# DC-DC_Bridge.net
KiCad netlist of a schematic drawn in Altium Designer
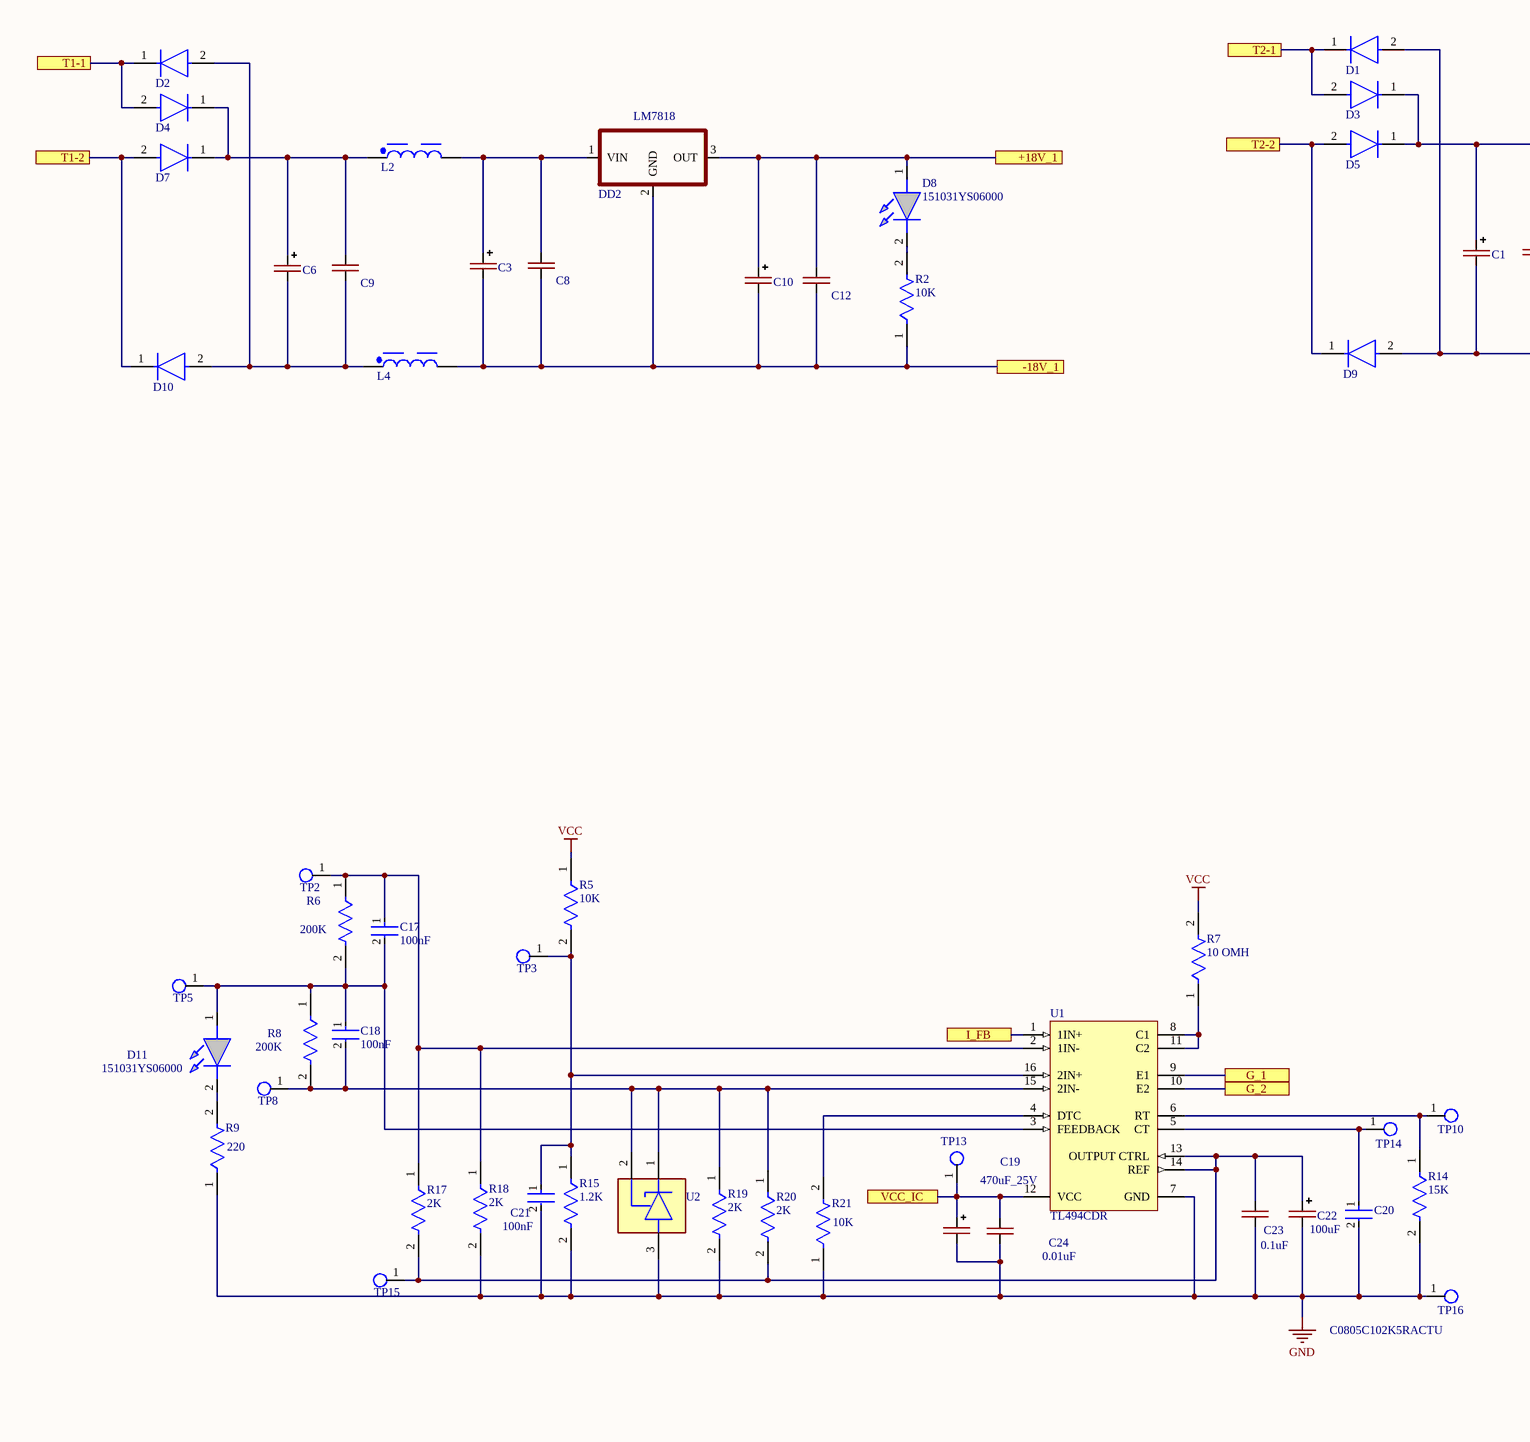
[diagram p0: DC-DC_Bridge.SchDoc, left]
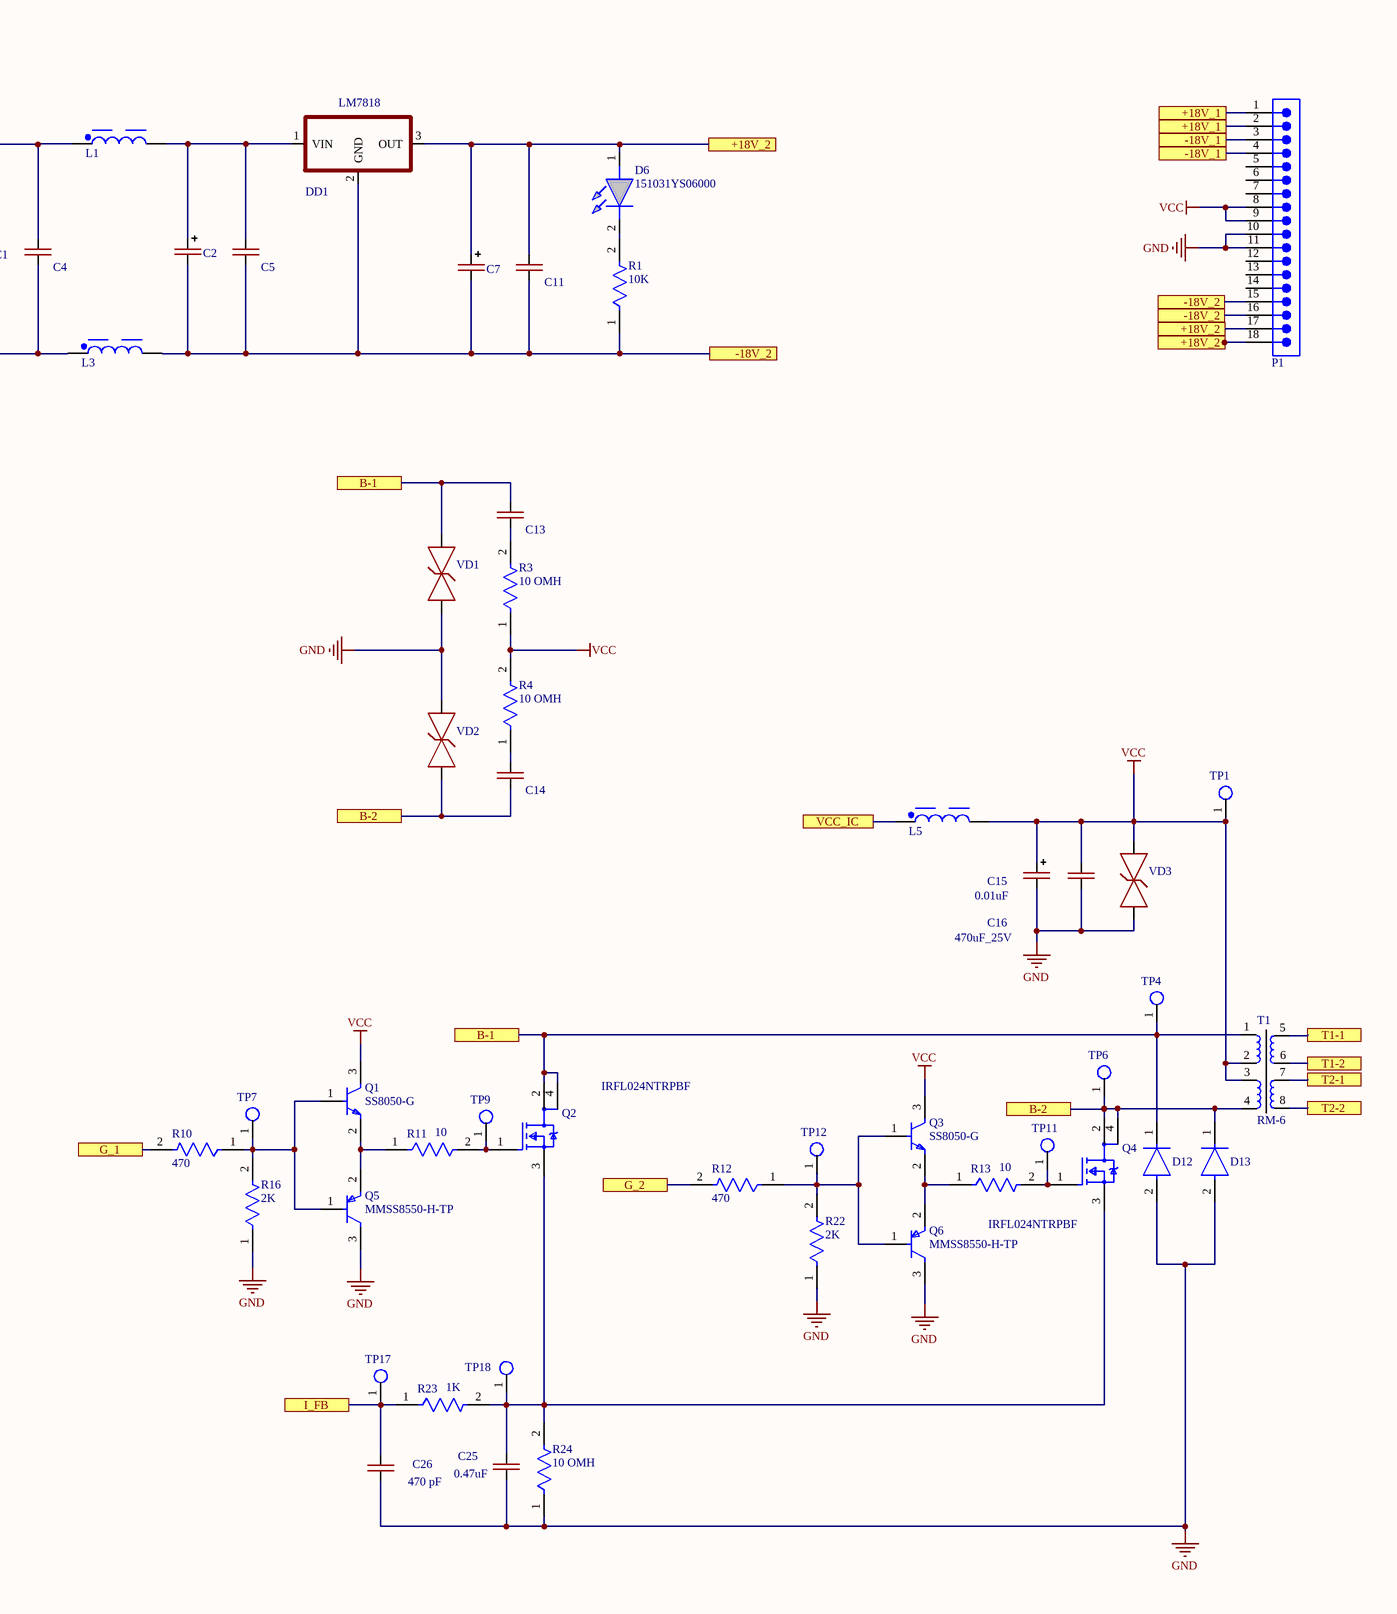
[diagram p1: DC-DC_Bridge.SchDoc, right]

(export (version "E")
  (design (tool "Eeschema 10.0.6"))
  (components
    (comp (ref "C1")
      (value "CAP-POLAR")
      (footprint "CAP_SMD_Size_G")
      (libsource (lib "PASSIVE_COMPONENTS") (part "CAP-POLAR"))
    )
    (comp (ref "C2")
      (value "CAP-POLAR")
      (footprint "CAP_SMD_Size_G")
      (libsource (lib "PASSIVE_COMPONENTS") (part "CAP-POLAR"))
    )
    (comp (ref "C3")
      (value "CAP-POLAR")
      (footprint "CAP_SMD_Size_G")
      (libsource (lib "PASSIVE_COMPONENTS") (part "CAP-POLAR"))
    )
    (comp (ref "C4")
      (value "CAP-NON-POLAR")
      (footprint "CAP-0805")
      (libsource (lib "PASSIVE_COMPONENTS") (part "CAP-NON-POLAR"))
    )
    (comp (ref "C5")
      (value "CAP-NON-POLAR")
      (footprint "CAP-0805")
      (libsource (lib "PASSIVE_COMPONENTS") (part "CAP-NON-POLAR"))
    )
    (comp (ref "C6")
      (value "CAP-POLAR")
      (footprint "CAP_SMD_Size_G")
      (libsource (lib "PASSIVE_COMPONENTS") (part "CAP-POLAR"))
    )
    (comp (ref "C7")
      (value "CAP-POLAR")
      (footprint "CAP_SMD_Size_G")
      (libsource (lib "PASSIVE_COMPONENTS") (part "CAP-POLAR"))
    )
    (comp (ref "C8")
      (value "CAP-NON-POLAR")
      (footprint "CAP-0805")
      (libsource (lib "PASSIVE_COMPONENTS") (part "CAP-NON-POLAR"))
    )
    (comp (ref "C9")
      (value "CAP-NON-POLAR")
      (footprint "CAP-0805")
      (libsource (lib "PASSIVE_COMPONENTS") (part "CAP-NON-POLAR"))
    )
    (comp (ref "C10")
      (value "CAP-POLAR")
      (footprint "CAP_SMD_Size_G")
      (libsource (lib "PASSIVE_COMPONENTS") (part "CAP-POLAR"))
    )
    (comp (ref "C11")
      (value "CAP-NON-POLAR")
      (footprint "CAP-0805")
      (libsource (lib "PASSIVE_COMPONENTS") (part "CAP-NON-POLAR"))
    )
    (comp (ref "C12")
      (value "CAP-NON-POLAR")
      (footprint "CAP-0805")
      (libsource (lib "PASSIVE_COMPONENTS") (part "CAP-NON-POLAR"))
    )
    (comp (ref "C13")
      (value "CAP-V")
      (footprint "CAP-V")
      (libsource (lib "PASSIVE_COMPONENTS") (part "CAP-V"))
    )
    (comp (ref "C14")
      (value "CAP-V")
      (footprint "CAP-V")
      (libsource (lib "PASSIVE_COMPONENTS") (part "CAP-V"))
    )
    (comp (ref "C15")
      (value "0.01uF")
      (footprint "CAP-0805")
      (libsource (lib "PASSIVE_COMPONENTS") (part "CAP-NON-POLAR"))
    )
    (comp (ref "C16")
      (value "470uF_25V")
      (footprint "CAP_SMD_Size_G")
      (libsource (lib "PASSIVE_COMPONENTS") (part "CAP-POLAR"))
    )
    (comp (ref "C17")
      (value "100nF")
      (footprint "FP-C0805C-DN-MFG")
      (description "CAP CER 10000PF 50V X7R 0805")
      (fields
        (field (name "MANUFACTURER PART NUMBER") "C0805C103J5RACTU")
        (field (name "MANUFACTURER") "KEMET")
      )
      (libsource (lib "Altium Content Vault") (part "b4654b650e69147ec39a6b967a45e02"))
    )
    (comp (ref "C18")
      (value "100nF")
      (footprint "FP-C0805C-DN-MFG")
      (description "CAP CER 10000PF 50V X7R 0805")
      (fields
        (field (name "MANUFACTURER PART NUMBER") "C0805C103J5RACTU")
        (field (name "MANUFACTURER") "KEMET")
      )
      (libsource (lib "Altium Content Vault") (part "b4654b650e69147ec39a6b967a45e02"))
    )
    (comp (ref "C19")
      (value "470uF_25V")
      (footprint "CAP_SMD_Size_G")
      (libsource (lib "PASSIVE_COMPONENTS") (part "CAP-POLAR"))
    )
    (comp (ref "C20")
      (value "C0805C102K5RACTU")
      (footprint "FP-C0805C-DN-MFG")
      (description "CAP CER 1000PF 50V X7R 0805")
      (fields
        (field (name "OCTOPART") "https://octopart.com/c0805c102k5ractu-kemet-93010")
        (field (name "TOLERANCE") "0.1")
      )
      (libsource (lib "Altium Content Vault") (part "b4654b650e69147ec39a6b967a45e02"))
    )
    (comp (ref "C21")
      (value "100nF")
      (footprint "FP-C0805C-DN-MFG")
      (description "CAP CER 10000PF 50V X7R 0805")
      (fields
        (field (name "MANUFACTURER PART NUMBER") "C0805C103J5RACTU")
        (field (name "MANUFACTURER") "KEMET")
      )
      (libsource (lib "Altium Content Vault") (part "b4654b650e69147ec39a6b967a45e02"))
    )
    (comp (ref "C22")
      (value "100uF")
      (footprint "CAP-TAN-D")
      (libsource (lib "PASSIVE_COMPONENTS") (part "CAP-POLAR"))
    )
    (comp (ref "C23")
      (value "0.1uF")
      (footprint "CAP-0805")
      (libsource (lib "PASSIVE_COMPONENTS") (part "CAP-NON-POLAR"))
    )
    (comp (ref "C24")
      (value "0.01uF")
      (footprint "CAP-0805")
      (libsource (lib "PASSIVE_COMPONENTS") (part "CAP-NON-POLAR"))
    )
    (comp (ref "C25")
      (value "0.47uF")
      (footprint "CAP-0805")
      (libsource (lib "PASSIVE_COMPONENTS") (part "CAP-NON-POLAR"))
    )
    (comp (ref "C26")
      (value "470 pF")
      (footprint "CAP-0805")
      (libsource (lib "PASSIVE_COMPONENTS") (part "CAP-NON-POLAR"))
    )
    (comp (ref "D1") (value "US1G") (footprint "DO-214AA") (libsource (lib "Diodes") (part "US1G")))
    (comp (ref "D2") (value "US1G") (footprint "DO-214AA") (libsource (lib "Diodes") (part "US1G")))
    (comp (ref "D3") (value "US1G") (footprint "DO-214AA") (libsource (lib "Diodes") (part "US1G")))
    (comp (ref "D4") (value "US1G") (footprint "DO-214AA") (libsource (lib "Diodes") (part "US1G")))
    (comp (ref "D5") (value "US1G") (footprint "DO-214AA") (libsource (lib "Diodes") (part "US1G")))
    (comp (ref "D6")
      (value "151031YS06000")
      (footprint "LED_RED")
      (description "WURTH ELEKTRONIK - 151031YS06000 - LED, Yellow, Through Hole, T-1 (3mm), 30 mA, 2 V, 590 nm")
      (fields (field (name "MOUSER PART NUMBER") "710-151031YS06000"))
      (libsource (lib "Optic-LED") (part "LED"))
    )
    (comp (ref "D7") (value "US1G") (footprint "DO-214AA") (libsource (lib "Diodes") (part "US1G")))
    (comp (ref "D8")
      (value "151031YS06000")
      (footprint "LED_RED")
      (description "WURTH ELEKTRONIK - 151031YS06000 - LED, Yellow, Through Hole, T-1 (3mm), 30 mA, 2 V, 590 nm")
      (fields (field (name "MOUSER PART NUMBER") "710-151031YS06000"))
      (libsource (lib "Optic-LED") (part "LED"))
    )
    (comp (ref "D9") (value "US1G") (footprint "DO-214AA") (libsource (lib "Diodes") (part "US1G")))
    (comp (ref "D10") (value "US1G") (footprint "DO-214AA") (libsource (lib "Diodes") (part "US1G")))
    (comp (ref "D11")
      (value "151031YS06000")
      (footprint "LED_RED")
      (description "WURTH ELEKTRONIK - 151031YS06000 - LED, Yellow, Through Hole, T-1 (3mm), 30 mA, 2 V, 590 nm")
      (fields (field (name "MOUSER PART NUMBER") "710-151031YS06000"))
      (libsource (lib "Optic-LED") (part "LED"))
    )
    (comp (ref "D12") (value "US1G") (footprint "DO-214AA") (libsource (lib "Diodes") (part "US1G")))
    (comp (ref "D13") (value "US1G") (footprint "DO-214AA") (libsource (lib "Diodes") (part "US1G")))
    (comp (ref "DD1")
      (value "LM7818")
      (footprint "TO-252")
      (libsource (lib "LM7818__TO-252") (part "LM7818"))
    )
    (comp (ref "DD2")
      (value "LM7818")
      (footprint "TO-252")
      (libsource (lib "LM7818__TO-252") (part "LM7818"))
    )
    (comp (ref "L1")
      (value "390µH, 0.38A")
      (footprint "WE-PD2_7850")
      (description "WE-PD2 SMT Power Inductor, size 7850, 390µH, 0.38A, 1.77Ω")
      (fields
        (field (name "MANUFACTURER PART NUMBER") "744775239")
        (field (name "MANUFACTURER") "Wurth Elektronik")
      )
      (libsource (lib "WE-PD2 (rev22d)") (part "744775239"))
    )
    (comp (ref "L2")
      (value "390µH, 0.38A")
      (footprint "WE-PD2_7850")
      (description "WE-PD2 SMT Power Inductor, size 7850, 390µH, 0.38A, 1.77Ω")
      (fields
        (field (name "MANUFACTURER PART NUMBER") "744775239")
        (field (name "MANUFACTURER") "Wurth Elektronik")
      )
      (libsource (lib "WE-PD2 (rev22d)") (part "744775239"))
    )
    (comp (ref "L3")
      (value "390µH, 0.38A")
      (footprint "WE-PD2_7850")
      (description "WE-PD2 SMT Power Inductor, size 7850, 390µH, 0.38A, 1.77Ω")
      (fields
        (field (name "MANUFACTURER PART NUMBER") "744775239")
        (field (name "MANUFACTURER") "Wurth Elektronik")
      )
      (libsource (lib "WE-PD2 (rev22d)") (part "744775239"))
    )
    (comp (ref "L4")
      (value "390µH, 0.38A")
      (footprint "WE-PD2_7850")
      (description "WE-PD2 SMT Power Inductor, size 7850, 390µH, 0.38A, 1.77Ω")
      (fields
        (field (name "MANUFACTURER PART NUMBER") "744775239")
        (field (name "MANUFACTURER") "Wurth Elektronik")
      )
      (libsource (lib "WE-PD2 (rev22d)") (part "744775239"))
    )
    (comp (ref "L5")
      (value "390µH, 0.38A")
      (footprint "WE-PD2_7850")
      (description "WE-PD2 SMT Power Inductor, size 7850, 390µH, 0.38A, 1.77Ω")
      (fields
        (field (name "MANUFACTURER PART NUMBER") "744775239")
        (field (name "MANUFACTURER") "Wurth Elektronik")
      )
      (libsource (lib "WE-PD2 (rev22d)") (part "744775239"))
    )
    (comp (ref "P1")
      (value "61301811021")
      (footprint "61301811021")
      (description "WR-PHD Pin Header, THT, Angled, pitch 2.54mm, 1 Row, 18P")
      (fields (field (name "MANUFACTURER") "Wurth Elektronik"))
      (libsource (lib "Altium_WR-PHD (rev22b)") (part "61301811021"))
    )
    (comp (ref "Q1")
      (value "SS8050-G")
      (footprint "FP-SS8050-G-MFG")
      (description "NPN TRANSISTOR 1.5A 40V SOT-23 R")
      (libsource (lib "Altium Content Vault") (part "2a1388f82443b098dcd57d24ac7632d"))
    )
    (comp (ref "Q2")
      (value "IRFL024NTRPBF")
      (footprint "FP-PG-SOT223-3-IPC_B")
      (description "MOSFET N-CH 55V 2.8A SOT223")
      (libsource (lib "Altium Content Vault") (part "7f70c8421781a2c4d0598199639518f"))
    )
    (comp (ref "Q3")
      (value "SS8050-G")
      (footprint "FP-SS8050-G-MFG")
      (description "NPN TRANSISTOR 1.5A 40V SOT-23 R")
      (libsource (lib "Altium Content Vault") (part "2a1388f82443b098dcd57d24ac7632d"))
    )
    (comp (ref "Q4")
      (value "IRFL024NTRPBF")
      (footprint "FP-PG-SOT223-3-IPC_B")
      (description "MOSFET N-CH 55V 2.8A SOT223")
      (libsource (lib "Altium Content Vault") (part "7f70c8421781a2c4d0598199639518f"))
    )
    (comp (ref "Q5")
      (value "MMSS8550-H-TP")
      (footprint "FP-SOT-23-IPC_B")
      (description "TRANS PNP 25V 1.5A SOT23")
      (libsource (lib "Altium Content Vault") (part "0e8486ed3b47d9c69b8404ba87cf0f7"))
    )
    (comp (ref "Q6")
      (value "MMSS8550-H-TP")
      (footprint "FP-SOT-23-IPC_B")
      (description "TRANS PNP 25V 1.5A SOT23")
      (libsource (lib "Altium Content Vault") (part "0e8486ed3b47d9c69b8404ba87cf0f7"))
    )
    (comp (ref "R1")
      (value "10K")
      (footprint "RES-0805")
      (libsource (lib "PASSIVE_COMPONENTS") (part "RES-CONST"))
    )
    (comp (ref "R2")
      (value "10K")
      (footprint "RES-0805")
      (libsource (lib "PASSIVE_COMPONENTS") (part "RES-CONST"))
    )
    (comp (ref "R3")
      (value "10 OMH")
      (footprint "RES-1206")
      (libsource (lib "PASSIVE_COMPONENTS") (part "RES-CONST"))
    )
    (comp (ref "R4")
      (value "10 OMH")
      (footprint "RES-1206")
      (libsource (lib "PASSIVE_COMPONENTS") (part "RES-CONST"))
    )
    (comp (ref "R5")
      (value "10K")
      (footprint "FP-CRCW0805-e3-MFG")
      (description "RES Thick Film, 2kΩ, 1%, 0.125W, 100ppm/°C, 0805")
      (fields (field (name "TOLERANCE") "1%"))
      (libsource (lib "Pasive_components") (part "CMP-2001-04908-2"))
    )
    (comp (ref "R6")
      (value "200K")
      (footprint "FP-CRCW0805-e3-MFG")
      (description "RES Thick Film, 2kΩ, 1%, 0.125W, 100ppm/°C, 0805")
      (fields (field (name "TOLERANCE") "1%"))
      (libsource (lib "Pasive_components") (part "CMP-2001-04908-2"))
    )
    (comp (ref "R7")
      (value "10 OMH")
      (footprint "RES-1206")
      (libsource (lib "PASSIVE_COMPONENTS") (part "RES-CONST"))
    )
    (comp (ref "R8")
      (value "200K")
      (footprint "FP-CRCW0805-e3-MFG")
      (description "RES Thick Film, 2kΩ, 1%, 0.125W, 100ppm/°C, 0805")
      (fields (field (name "TOLERANCE") "1%"))
      (libsource (lib "Pasive_components") (part "CMP-2001-04908-2"))
    )
    (comp (ref "R9")
      (value "220")
      (footprint "RES-0805")
      (libsource (lib "PASSIVE_COMPONENTS") (part "RES-CONST"))
    )
    (comp (ref "R10")
      (value "470")
      (footprint "RES-0805")
      (libsource (lib "PASSIVE_COMPONENTS") (part "RES-CONST"))
    )
    (comp (ref "R11")
      (value "10")
      (footprint "RES-0805")
      (libsource (lib "PASSIVE_COMPONENTS") (part "RES-CONST"))
    )
    (comp (ref "R12")
      (value "470")
      (footprint "RES-0805")
      (libsource (lib "PASSIVE_COMPONENTS") (part "RES-CONST"))
    )
    (comp (ref "R13")
      (value "10")
      (footprint "RES-0805")
      (libsource (lib "PASSIVE_COMPONENTS") (part "RES-CONST"))
    )
    (comp (ref "R14")
      (value "15K")
      (footprint "FP-CRCW0805-e3-MFG")
      (description "RES Thick Film, 15kΩ, 1%, 0.125W, 100ppm/°C, 0805")
      (fields (field (name "TOLERANCE") "1%"))
      (libsource (lib "Pasive_components") (part "CMP-2001-04908-2"))
    )
    (comp (ref "R15")
      (value "1.2K")
      (footprint "FP-CRCW0805-e3-MFG")
      (description "RES Thick Film, 2kΩ, 1%, 0.125W, 100ppm/°C, 0805")
      (fields (field (name "TOLERANCE") "1%"))
      (libsource (lib "Pasive_components") (part "CMP-2001-04908-2"))
    )
    (comp (ref "R16")
      (value "2K")
      (footprint "RES-0805")
      (libsource (lib "PASSIVE_COMPONENTS") (part "RES-CONST"))
    )
    (comp (ref "R17")
      (value "2K")
      (footprint "FP-CRCW0805-e3-MFG")
      (description "RES Thick Film, 2kΩ, 1%, 0.125W, 100ppm/°C, 0805")
      (fields (field (name "TOLERANCE") "1%"))
      (libsource (lib "Pasive_components") (part "CMP-2001-04908-2"))
    )
    (comp (ref "R18")
      (value "2K")
      (footprint "FP-CRCW0805-e3-MFG")
      (description "RES Thick Film, 82kΩ, 1%, 0.125W, 100ppm/°C, 0805")
      (fields (field (name "TOLERANCE") "1%"))
      (libsource (lib "Pasive_components") (part "CMP-2001-04908-2"))
    )
    (comp (ref "R19")
      (value "2K")
      (footprint "FP-CRCW0805-e3-MFG")
      (description "RES Thick Film, 2kΩ, 1%, 0.125W, 100ppm/°C, 0805")
      (fields (field (name "TOLERANCE") "1%"))
      (libsource (lib "Pasive_components") (part "CMP-2001-04908-2"))
    )
    (comp (ref "R20")
      (value "2K")
      (footprint "FP-CRCW0805-e3-MFG")
      (description "RES Thick Film, 2kΩ, 1%, 0.125W, 100ppm/°C, 0805")
      (fields (field (name "TOLERANCE") "1%"))
      (libsource (lib "Pasive_components") (part "CMP-2001-04908-2"))
    )
    (comp (ref "R21")
      (value "10K")
      (footprint "RES-0805")
      (libsource (lib "PASSIVE_COMPONENTS") (part "RES-CONST"))
    )
    (comp (ref "R22")
      (value "2K")
      (footprint "RES-0805")
      (libsource (lib "PASSIVE_COMPONENTS") (part "RES-CONST"))
    )
    (comp (ref "R23")
      (value "1K")
      (footprint "RES-0805")
      (libsource (lib "PASSIVE_COMPONENTS") (part "RES-CONST"))
    )
    (comp (ref "R24")
      (value "10 OMH")
      (footprint "RES-2512")
      (libsource (lib "PASSIVE_COMPONENTS") (part "RES-CONST"))
    )
    (comp (ref "T1")
      (value "RM-6")
      (footprint "TRANS_RM6")
      (libsource (lib "Transformers") (part "RM_6_12-12-18-18"))
    )
    (comp (ref "TP1")
      (value "~")
      (footprint "Test_Point")
      (description "Test_Point")
      (libsource (lib "Connectors") (part "TP_PCB?"))
    )
    (comp (ref "TP2")
      (value "Test_Point_PCB")
      (footprint "Test_Point")
      (description "Test_Point")
      (libsource (lib "Test_Point") (part "TP_PCB?"))
    )
    (comp (ref "TP3")
      (value "Test_Point_PCB")
      (footprint "Test_Point")
      (description "Test_Point")
      (libsource (lib "Test_Point") (part "TP_PCB?"))
    )
    (comp (ref "TP4")
      (value "~")
      (footprint "Test_Point")
      (description "Test_Point")
      (libsource (lib "Connectors") (part "TP_PCB?"))
    )
    (comp (ref "TP5")
      (value "Test_Point_PCB")
      (footprint "Test_Point")
      (description "Test_Point")
      (libsource (lib "Test_Point") (part "TP_PCB?"))
    )
    (comp (ref "TP6")
      (value "~")
      (footprint "Test_Point")
      (description "Test_Point")
      (libsource (lib "Connectors") (part "TP_PCB?"))
    )
    (comp (ref "TP7")
      (value "~")
      (footprint "Test_Point")
      (description "Test_Point")
      (libsource (lib "Connectors") (part "TP_PCB?"))
    )
    (comp (ref "TP8")
      (value "~")
      (footprint "Test_Point")
      (description "Test_Point")
      (libsource (lib "Connectors") (part "TP_PCB?"))
    )
    (comp (ref "TP9")
      (value "~")
      (footprint "Test_Point")
      (description "Test_Point")
      (libsource (lib "Connectors") (part "TP_PCB?"))
    )
    (comp (ref "TP10")
      (value "~")
      (footprint "Test_Point")
      (description "Test_Point")
      (libsource (lib "Connectors") (part "TP_PCB?"))
    )
    (comp (ref "TP11")
      (value "~")
      (footprint "Test_Point")
      (description "Test_Point")
      (libsource (lib "Connectors") (part "TP_PCB?"))
    )
    (comp (ref "TP12")
      (value "~")
      (footprint "Test_Point")
      (description "Test_Point")
      (libsource (lib "Connectors") (part "TP_PCB?"))
    )
    (comp (ref "TP13")
      (value "~")
      (footprint "Test_Point")
      (description "Test_Point")
      (libsource (lib "Connectors") (part "TP_PCB?"))
    )
    (comp (ref "TP14")
      (value "Test_Point_PCB")
      (footprint "Test_Point")
      (description "Test_Point")
      (libsource (lib "Test_Point") (part "TP_PCB?"))
    )
    (comp (ref "TP15")
      (value "Test_Point_PCB")
      (footprint "Test_Point")
      (description "Test_Point")
      (libsource (lib "Test_Point") (part "TP_PCB?"))
    )
    (comp (ref "TP16")
      (value "~")
      (footprint "Test_Point")
      (description "Test_Point")
      (libsource (lib "Connectors") (part "TP_PCB?"))
    )
    (comp (ref "TP17")
      (value "~")
      (footprint "Test_Point")
      (description "Test_Point")
      (libsource (lib "Connectors") (part "TP_PCB?"))
    )
    (comp (ref "TP18")
      (value "~")
      (footprint "Test_Point")
      (description "Test_Point")
      (libsource (lib "Connectors") (part "TP_PCB?"))
    )
    (comp (ref "U1")
      (value "TL494CDR")
      (footprint "D0016A_N")
      (fields (field (name "MANUFACTURER") "Texas Instruments"))
      (libsource (lib "Altium Content Vault") (part "TI-494D16"))
    )
    (comp (ref "U2")
      (value "TL431")
      (footprint "TL431_SOT-23-3(A)")
      (description "TL431_SOT-23-3")
      (libsource (lib "Diodes") (part "TL431_SOT-23-3"))
    )
    (comp (ref "VD1")
      (value "Suppressor")
      (footprint "P6KE350CA")
      (libsource (lib "Diodes") (part "Suppressor"))
    )
    (comp (ref "VD2")
      (value "Suppressor")
      (footprint "P6KE350CA")
      (libsource (lib "Diodes") (part "Suppressor"))
    )
    (comp (ref "VD3")
      (value "Suppressor")
      (footprint "DO-214AA")
      (libsource (lib "Diodes") (part "Suppressor"))
    )
  )
  (nets
    (net (code "1") (name "/+18V_1") (class "Default")
      (node (ref "C10") (pin "1") (pinfunction "+_1") (pintype "passive"))
      (node (ref "C12") (pin "2") (pinfunction "2_2") (pintype "passive"))
      (node (ref "D8") (pin "1") (pinfunction "A_1") (pintype "passive"))
      (node (ref "DD2") (pin "3") (pinfunction "OUT_3") (pintype "passive"))
      (node (ref "P1") (pin "1") (pinfunction "1_1") (pintype "passive"))
      (node (ref "P1") (pin "2") (pinfunction "2_2") (pintype "passive"))
    )
    (net (code "2") (name "/+18V_2") (class "Default")
      (node (ref "C11") (pin "2") (pinfunction "2_2") (pintype "passive"))
      (node (ref "C7") (pin "1") (pinfunction "+_1") (pintype "passive"))
      (node (ref "D6") (pin "1") (pinfunction "A_1") (pintype "passive"))
      (node (ref "DD1") (pin "3") (pinfunction "OUT_3") (pintype "passive"))
      (node (ref "P1") (pin "17") (pinfunction "17_17") (pintype "passive"))
      (node (ref "P1") (pin "18") (pinfunction "18_18") (pintype "passive"))
    )
    (net (code "3") (name "/-18V_1") (class "Default")
      (node (ref "C10") (pin "2") (pinfunction "-_2") (pintype "passive"))
      (node (ref "C12") (pin "1") (pinfunction "1_1") (pintype "passive"))
      (node (ref "C3") (pin "2") (pinfunction "-_2") (pintype "passive"))
      (node (ref "C8") (pin "1") (pinfunction "1_1") (pintype "passive"))
      (node (ref "DD2") (pin "2") (pinfunction "GND_2") (pintype "passive"))
      (node (ref "L4") (pin "2") (pinfunction "2_2") (pintype "passive"))
      (node (ref "P1") (pin "3") (pinfunction "3_3") (pintype "passive"))
      (node (ref "P1") (pin "4") (pinfunction "4_4") (pintype "passive"))
      (node (ref "R2") (pin "1") (pinfunction "1_1") (pintype "passive"))
    )
    (net (code "4") (name "/-18V_2") (class "Default")
      (node (ref "C11") (pin "1") (pinfunction "1_1") (pintype "passive"))
      (node (ref "C2") (pin "2") (pinfunction "-_2") (pintype "passive"))
      (node (ref "C5") (pin "1") (pinfunction "1_1") (pintype "passive"))
      (node (ref "C7") (pin "2") (pinfunction "-_2") (pintype "passive"))
      (node (ref "DD1") (pin "2") (pinfunction "GND_2") (pintype "passive"))
      (node (ref "L3") (pin "2") (pinfunction "2_2") (pintype "passive"))
      (node (ref "P1") (pin "15") (pinfunction "15_15") (pintype "passive"))
      (node (ref "P1") (pin "16") (pinfunction "16_16") (pintype "passive"))
      (node (ref "R1") (pin "1") (pinfunction "1_1") (pintype "passive"))
    )
    (net (code "5") (name "/B-1") (class "Default")
      (node (ref "C13") (pin "2") (pinfunction "2_2") (pintype "passive"))
      (node (ref "D12") (pin "1") (pinfunction "C_1") (pintype "passive"))
      (node (ref "Q2") (pin "2") (pinfunction "D_2") (pintype "passive"))
      (node (ref "Q2") (pin "4") (pinfunction "D_4") (pintype "passive"))
      (node (ref "T1") (pin "1") (pinfunction "1_1") (pintype "passive"))
      (node (ref "TP4") (pin "1") (pinfunction "G9_1") (pintype "passive"))
      (node (ref "VD1") (pin "2") (pinfunction "A_2") (pintype "passive"))
    )
    (net (code "6") (name "/B-2") (class "Default")
      (node (ref "C14") (pin "1") (pinfunction "1_1") (pintype "passive"))
      (node (ref "D13") (pin "1") (pinfunction "C_1") (pintype "passive"))
      (node (ref "Q4") (pin "2") (pinfunction "D_2") (pintype "passive"))
      (node (ref "Q4") (pin "4") (pinfunction "D_4") (pintype "passive"))
      (node (ref "T1") (pin "4") (pinfunction "4_4") (pintype "passive"))
      (node (ref "TP6") (pin "1") (pinfunction "G9_1") (pintype "passive"))
      (node (ref "VD2") (pin "1") (pinfunction "C_1") (pintype "passive"))
    )
    (net (code "7") (name "/G_1") (class "Default")
      (node (ref "R10") (pin "2") (pinfunction "2_2") (pintype "passive"))
      (node (ref "U1") (pin "9") (pinfunction "E1_9") (pintype "passive"))
    )
    (net (code "8") (name "/G_2") (class "Default")
      (node (ref "R12") (pin "2") (pinfunction "2_2") (pintype "passive"))
      (node (ref "U1") (pin "10") (pinfunction "E2_10") (pintype "passive"))
    )
    (net (code "9") (name "/I_FB") (class "Default")
      (node (ref "C26") (pin "2") (pinfunction "2_2") (pintype "passive"))
      (node (ref "R23") (pin "1") (pinfunction "1_1") (pintype "passive"))
      (node (ref "TP17") (pin "1") (pinfunction "G9_1") (pintype "passive"))
      (node (ref "U1") (pin "1") (pinfunction "1IN+_1") (pintype "input"))
    )
    (net (code "10") (name "/T1-1") (class "Default")
      (node (ref "D2") (pin "1") (pinfunction "C_1") (pintype "passive"))
      (node (ref "D4") (pin "2") (pinfunction "A_2") (pintype "passive"))
      (node (ref "T1") (pin "5") (pinfunction "5_5") (pintype "passive"))
    )
    (net (code "11") (name "/T1-2") (class "Default")
      (node (ref "D10") (pin "1") (pinfunction "C_1") (pintype "passive"))
      (node (ref "D7") (pin "2") (pinfunction "A_2") (pintype "passive"))
      (node (ref "T1") (pin "6") (pinfunction "6_6") (pintype "passive"))
    )
    (net (code "12") (name "/T2-1") (class "Default")
      (node (ref "D1") (pin "1") (pinfunction "C_1") (pintype "passive"))
      (node (ref "D3") (pin "2") (pinfunction "A_2") (pintype "passive"))
      (node (ref "T1") (pin "7") (pinfunction "7_7") (pintype "passive"))
    )
    (net (code "13") (name "/T2-2") (class "Default")
      (node (ref "D5") (pin "2") (pinfunction "A_2") (pintype "passive"))
      (node (ref "D9") (pin "1") (pinfunction "C_1") (pintype "passive"))
      (node (ref "T1") (pin "8") (pinfunction "8_8") (pintype "passive"))
    )
    (net (code "14") (name "/VCC_IC") (class "Default")
      (node (ref "C19") (pin "1") (pinfunction "+_1") (pintype "passive"))
      (node (ref "C24") (pin "2") (pinfunction "2_2") (pintype "passive"))
      (node (ref "L5") (pin "1") (pinfunction "1_1") (pintype "passive"))
      (node (ref "TP13") (pin "1") (pinfunction "G9_1") (pintype "passive"))
      (node (ref "U1") (pin "12") (pinfunction "VCC_12") (pintype "power_in"))
    )
    (net (code "15") (name "GND") (class "Default")
      (node (ref "C15") (pin "1") (pinfunction "1_1") (pintype "passive"))
      (node (ref "C16") (pin "2") (pinfunction "-_2") (pintype "passive"))
      (node (ref "C19") (pin "2") (pinfunction "-_2") (pintype "passive"))
      (node (ref "C20") (pin "2") (pinfunction "2_2") (pintype "passive"))
      (node (ref "C21") (pin "2") (pinfunction "2_2") (pintype "passive"))
      (node (ref "C22") (pin "2") (pinfunction "-_2") (pintype "passive"))
      (node (ref "C23") (pin "1") (pinfunction "1_1") (pintype "passive"))
      (node (ref "C24") (pin "1") (pinfunction "1_1") (pintype "passive"))
      (node (ref "C25") (pin "1") (pinfunction "1_1") (pintype "passive"))
      (node (ref "C26") (pin "1") (pinfunction "1_1") (pintype "passive"))
      (node (ref "D12") (pin "2") (pinfunction "A_2") (pintype "passive"))
      (node (ref "D13") (pin "2") (pinfunction "A_2") (pintype "passive"))
      (node (ref "P1") (pin "10") (pinfunction "10_10") (pintype "passive"))
      (node (ref "P1") (pin "11") (pinfunction "11_11") (pintype "passive"))
      (node (ref "Q5") (pin "3") (pinfunction "C_3") (pintype "passive"))
      (node (ref "Q6") (pin "3") (pinfunction "C_3") (pintype "passive"))
      (node (ref "R14") (pin "2") (pinfunction "2_2") (pintype "passive"))
      (node (ref "R15") (pin "2") (pinfunction "2_2") (pintype "passive"))
      (node (ref "R16") (pin "1") (pinfunction "1_1") (pintype "passive"))
      (node (ref "R18") (pin "2") (pinfunction "2_2") (pintype "passive"))
      (node (ref "R19") (pin "2") (pinfunction "2_2") (pintype "passive"))
      (node (ref "R21") (pin "1") (pinfunction "1_1") (pintype "passive"))
      (node (ref "R22") (pin "1") (pinfunction "1_1") (pintype "passive"))
      (node (ref "R24") (pin "1") (pinfunction "1_1") (pintype "passive"))
      (node (ref "R9") (pin "1") (pinfunction "1_1") (pintype "passive"))
      (node (ref "TP16") (pin "1") (pinfunction "G9_1") (pintype "passive"))
      (node (ref "U1") (pin "7") (pinfunction "GND_7") (pintype "power_in"))
      (node (ref "U2") (pin "3") (pinfunction "A_3") (pintype "passive"))
      (node (ref "VD1") (pin "1") (pinfunction "C_1") (pintype "passive"))
      (node (ref "VD2") (pin "2") (pinfunction "A_2") (pintype "passive"))
      (node (ref "VD3") (pin "1") (pinfunction "C_1") (pintype "passive"))
    )
    (net (code "16") (name "Net-(C1-+)") (class "Default")
      (node (ref "C1") (pin "1") (pinfunction "+_1") (pintype "passive"))
      (node (ref "C4") (pin "2") (pinfunction "2_2") (pintype "passive"))
      (node (ref "D3") (pin "1") (pinfunction "C_1") (pintype "passive"))
      (node (ref "D5") (pin "1") (pinfunction "C_1") (pintype "passive"))
      (node (ref "L1") (pin "1") (pinfunction "1_1") (pintype "passive"))
    )
    (net (code "17") (name "Net-(C1--)") (class "Default")
      (node (ref "C1") (pin "2") (pinfunction "-_2") (pintype "passive"))
      (node (ref "C4") (pin "1") (pinfunction "1_1") (pintype "passive"))
      (node (ref "D1") (pin "2") (pinfunction "A_2") (pintype "passive"))
      (node (ref "D9") (pin "2") (pinfunction "A_2") (pintype "passive"))
      (node (ref "L3") (pin "1") (pinfunction "1_1") (pintype "passive"))
    )
    (net (code "18") (name "Net-(C2-+)") (class "Default")
      (node (ref "C2") (pin "1") (pinfunction "+_1") (pintype "passive"))
      (node (ref "C5") (pin "2") (pinfunction "2_2") (pintype "passive"))
      (node (ref "DD1") (pin "1") (pinfunction "VIN_1") (pintype "passive"))
      (node (ref "L1") (pin "2") (pinfunction "2_2") (pintype "passive"))
    )
    (net (code "19") (name "Net-(C3-+)") (class "Default")
      (node (ref "C3") (pin "1") (pinfunction "+_1") (pintype "passive"))
      (node (ref "C8") (pin "2") (pinfunction "2_2") (pintype "passive"))
      (node (ref "DD2") (pin "1") (pinfunction "VIN_1") (pintype "passive"))
      (node (ref "L2") (pin "2") (pinfunction "2_2") (pintype "passive"))
    )
    (net (code "20") (name "Net-(C6-+)") (class "Default")
      (node (ref "C6") (pin "1") (pinfunction "+_1") (pintype "passive"))
      (node (ref "C9") (pin "2") (pinfunction "2_2") (pintype "passive"))
      (node (ref "D4") (pin "1") (pinfunction "C_1") (pintype "passive"))
      (node (ref "D7") (pin "1") (pinfunction "C_1") (pintype "passive"))
      (node (ref "L2") (pin "1") (pinfunction "1_1") (pintype "passive"))
    )
    (net (code "21") (name "Net-(C6--)") (class "Default")
      (node (ref "C6") (pin "2") (pinfunction "-_2") (pintype "passive"))
      (node (ref "C9") (pin "1") (pinfunction "1_1") (pintype "passive"))
      (node (ref "D10") (pin "2") (pinfunction "A_2") (pintype "passive"))
      (node (ref "D2") (pin "2") (pinfunction "A_2") (pintype "passive"))
      (node (ref "L4") (pin "1") (pinfunction "1_1") (pintype "passive"))
    )
    (net (code "22") (name "Net-(C13-Pad1)") (class "Default")
      (node (ref "C13") (pin "1") (pinfunction "1_1") (pintype "passive"))
      (node (ref "R3") (pin "2") (pinfunction "2_2") (pintype "passive"))
    )
    (net (code "23") (name "Net-(C14-Pad2)") (class "Default")
      (node (ref "C14") (pin "2") (pinfunction "2_2") (pintype "passive"))
      (node (ref "R4") (pin "1") (pinfunction "1_1") (pintype "passive"))
    )
    (net (code "24") (name "Net-(C22-+)") (class "Default")
      (node (ref "C22") (pin "1") (pinfunction "+_1") (pintype "passive"))
      (node (ref "C23") (pin "2") (pinfunction "2_2") (pintype "passive"))
      (node (ref "R17") (pin "2") (pinfunction "2_2") (pintype "passive"))
      (node (ref "R20") (pin "2") (pinfunction "2_2") (pintype "passive"))
      (node (ref "TP15") (pin "1") (pinfunction "G9_1") (pintype "passive"))
      (node (ref "U1") (pin "13") (pinfunction "OUTPUT_CTRL_13") (pintype "input"))
      (node (ref "U1") (pin "14") (pinfunction "REF_14") (pintype "output"))
    )
    (net (code "25") (name "Net-(D6-K)") (class "Default")
      (node (ref "D6") (pin "2") (pinfunction "K_2") (pintype "passive"))
      (node (ref "R1") (pin "2") (pinfunction "2_2") (pintype "passive"))
    )
    (net (code "26") (name "Net-(D8-K)") (class "Default")
      (node (ref "D8") (pin "2") (pinfunction "K_2") (pintype "passive"))
      (node (ref "R2") (pin "2") (pinfunction "2_2") (pintype "passive"))
    )
    (net (code "27") (name "Net-(D11-A)") (class "Default")
      (node (ref "C17") (pin "2") (pinfunction "2_2") (pintype "passive"))
      (node (ref "C18") (pin "1") (pinfunction "1_1") (pintype "passive"))
      (node (ref "D11") (pin "1") (pinfunction "A_1") (pintype "passive"))
      (node (ref "R6") (pin "2") (pinfunction "2_2") (pintype "passive"))
      (node (ref "R8") (pin "1") (pinfunction "1_1") (pintype "passive"))
      (node (ref "TP5") (pin "1") (pinfunction "G9_1") (pintype "passive"))
      (node (ref "U1") (pin "3") (pinfunction "FEEDBACK_3") (pintype "input"))
    )
    (net (code "28") (name "Net-(D11-K)") (class "Default")
      (node (ref "D11") (pin "2") (pinfunction "K_2") (pintype "passive"))
      (node (ref "R9") (pin "2") (pinfunction "2_2") (pintype "passive"))
    )
    (net (code "29") (name "Net-(Q1-B)") (class "Default")
      (node (ref "Q1") (pin "1") (pinfunction "B_1") (pintype "passive"))
      (node (ref "Q5") (pin "1") (pinfunction "B_1") (pintype "passive"))
      (node (ref "R10") (pin "1") (pinfunction "1_1") (pintype "passive"))
      (node (ref "R16") (pin "2") (pinfunction "2_2") (pintype "passive"))
      (node (ref "TP7") (pin "1") (pinfunction "G9_1") (pintype "passive"))
    )
    (net (code "30") (name "Net-(Q1-E)") (class "Default")
      (node (ref "Q1") (pin "2") (pinfunction "E_2") (pintype "passive"))
      (node (ref "Q5") (pin "2") (pinfunction "E_2") (pintype "passive"))
      (node (ref "R11") (pin "1") (pinfunction "1_1") (pintype "passive"))
    )
    (net (code "31") (name "Net-(Q2-G)") (class "Default")
      (node (ref "Q2") (pin "1") (pinfunction "G_1") (pintype "passive"))
      (node (ref "R11") (pin "2") (pinfunction "2_2") (pintype "passive"))
      (node (ref "TP9") (pin "1") (pinfunction "G9_1") (pintype "passive"))
    )
    (net (code "32") (name "Net-(Q2-S)") (class "Default")
      (node (ref "C25") (pin "2") (pinfunction "2_2") (pintype "passive"))
      (node (ref "Q2") (pin "3") (pinfunction "S_3") (pintype "passive"))
      (node (ref "Q4") (pin "3") (pinfunction "S_3") (pintype "passive"))
      (node (ref "R23") (pin "2") (pinfunction "2_2") (pintype "passive"))
      (node (ref "R24") (pin "2") (pinfunction "2_2") (pintype "passive"))
      (node (ref "TP18") (pin "1") (pinfunction "G9_1") (pintype "passive"))
    )
    (net (code "33") (name "Net-(Q3-B)") (class "Default")
      (node (ref "Q3") (pin "1") (pinfunction "B_1") (pintype "passive"))
      (node (ref "Q6") (pin "1") (pinfunction "B_1") (pintype "passive"))
      (node (ref "R12") (pin "1") (pinfunction "1_1") (pintype "passive"))
      (node (ref "R22") (pin "2") (pinfunction "2_2") (pintype "passive"))
      (node (ref "TP12") (pin "1") (pinfunction "G9_1") (pintype "passive"))
    )
    (net (code "34") (name "Net-(Q3-E)") (class "Default")
      (node (ref "Q3") (pin "2") (pinfunction "E_2") (pintype "passive"))
      (node (ref "Q6") (pin "2") (pinfunction "E_2") (pintype "passive"))
      (node (ref "R13") (pin "1") (pinfunction "1_1") (pintype "passive"))
    )
    (net (code "35") (name "Net-(Q4-G)") (class "Default")
      (node (ref "Q4") (pin "1") (pinfunction "G_1") (pintype "passive"))
      (node (ref "R13") (pin "2") (pinfunction "2_2") (pintype "passive"))
      (node (ref "TP11") (pin "1") (pinfunction "G9_1") (pintype "passive"))
    )
    (net (code "36") (name "Net-(TP2-G9)") (class "Default")
      (node (ref "C17") (pin "1") (pinfunction "1_1") (pintype "passive"))
      (node (ref "R17") (pin "1") (pinfunction "1_1") (pintype "passive"))
      (node (ref "R18") (pin "1") (pinfunction "1_1") (pintype "passive"))
      (node (ref "R6") (pin "1") (pinfunction "1_1") (pintype "passive"))
      (node (ref "TP2") (pin "1") (pinfunction "G9_1") (pintype "passive"))
      (node (ref "U1") (pin "2") (pinfunction "1IN-_2") (pintype "input"))
    )
    (net (code "37") (name "Net-(TP3-G9)") (class "Default")
      (node (ref "C21") (pin "1") (pinfunction "1_1") (pintype "passive"))
      (node (ref "R15") (pin "1") (pinfunction "1_1") (pintype "passive"))
      (node (ref "R5") (pin "2") (pinfunction "2_2") (pintype "passive"))
      (node (ref "TP3") (pin "1") (pinfunction "G9_1") (pintype "passive"))
      (node (ref "U1") (pin "16") (pinfunction "2IN+_16") (pintype "input"))
    )
    (net (code "38") (name "Net-(TP8-G9)") (class "Default")
      (node (ref "C18") (pin "2") (pinfunction "2_2") (pintype "passive"))
      (node (ref "R19") (pin "1") (pinfunction "1_1") (pintype "passive"))
      (node (ref "R20") (pin "1") (pinfunction "1_1") (pintype "passive"))
      (node (ref "R8") (pin "2") (pinfunction "2_2") (pintype "passive"))
      (node (ref "TP8") (pin "1") (pinfunction "G9_1") (pintype "passive"))
      (node (ref "U1") (pin "15") (pinfunction "2IN-_15") (pintype "input"))
      (node (ref "U2") (pin "1") (pinfunction "C_1") (pintype "passive"))
      (node (ref "U2") (pin "2") (pinfunction "REF_2") (pintype "passive"))
    )
    (net (code "39") (name "Net-(TP10-G9)") (class "Default")
      (node (ref "R14") (pin "1") (pinfunction "1_1") (pintype "passive"))
      (node (ref "TP10") (pin "1") (pinfunction "G9_1") (pintype "passive"))
      (node (ref "U1") (pin "6") (pinfunction "RT_6") (pintype "passive"))
    )
    (net (code "40") (name "Net-(TP14-G9)") (class "Default")
      (node (ref "C20") (pin "1") (pinfunction "1_1") (pintype "passive"))
      (node (ref "TP14") (pin "1") (pinfunction "G9_1") (pintype "passive"))
      (node (ref "U1") (pin "5") (pinfunction "CT_5") (pintype "passive"))
    )
    (net (code "41") (name "Net-(U1-C1)") (class "Default")
      (node (ref "R7") (pin "1") (pinfunction "1_1") (pintype "passive"))
      (node (ref "U1") (pin "11") (pinfunction "C2_11") (pintype "passive"))
      (node (ref "U1") (pin "8") (pinfunction "C1_8") (pintype "passive"))
    )
    (net (code "42") (name "Net-(U1-DTC)") (class "Default")
      (node (ref "R21") (pin "2") (pinfunction "2_2") (pintype "passive"))
      (node (ref "U1") (pin "4") (pinfunction "DTC_4") (pintype "input"))
    )
    (net (code "43") (name "VCC") (class "Default")
      (node (ref "C15") (pin "2") (pinfunction "2_2") (pintype "passive"))
      (node (ref "C16") (pin "1") (pinfunction "+_1") (pintype "passive"))
      (node (ref "L5") (pin "2") (pinfunction "2_2") (pintype "passive"))
      (node (ref "P1") (pin "8") (pinfunction "8_8") (pintype "passive"))
      (node (ref "P1") (pin "9") (pinfunction "9_9") (pintype "passive"))
      (node (ref "Q1") (pin "3") (pinfunction "C_3") (pintype "passive"))
      (node (ref "Q3") (pin "3") (pinfunction "C_3") (pintype "passive"))
      (node (ref "R3") (pin "1") (pinfunction "1_1") (pintype "passive"))
      (node (ref "R4") (pin "2") (pinfunction "2_2") (pintype "passive"))
      (node (ref "R5") (pin "1") (pinfunction "1_1") (pintype "passive"))
      (node (ref "R7") (pin "2") (pinfunction "2_2") (pintype "passive"))
      (node (ref "T1") (pin "2") (pinfunction "2_2") (pintype "passive"))
      (node (ref "T1") (pin "3") (pinfunction "3_3") (pintype "passive"))
      (node (ref "TP1") (pin "1") (pinfunction "G9_1") (pintype "passive"))
      (node (ref "VD3") (pin "2") (pinfunction "A_2") (pintype "passive"))
    )
    (net (code "44") (name "unconnected-(P1-Pad5)") (class "Default")
      (node (ref "P1") (pin "5") (pinfunction "5_5") (pintype "passive"))
    )
    (net (code "45") (name "unconnected-(P1-Pad6)") (class "Default")
      (node (ref "P1") (pin "6") (pinfunction "6_6") (pintype "passive"))
    )
    (net (code "46") (name "unconnected-(P1-Pad7)") (class "Default")
      (node (ref "P1") (pin "7") (pinfunction "7_7") (pintype "passive"))
    )
    (net (code "47") (name "unconnected-(P1-Pad12)") (class "Default")
      (node (ref "P1") (pin "12") (pinfunction "12_12") (pintype "passive"))
    )
    (net (code "48") (name "unconnected-(P1-Pad13)") (class "Default")
      (node (ref "P1") (pin "13") (pinfunction "13_13") (pintype "passive"))
    )
    (net (code "49") (name "unconnected-(P1-Pad14)") (class "Default")
      (node (ref "P1") (pin "14") (pinfunction "14_14") (pintype "passive"))
    )
  )
)
